# joystick_shield.net
KiCad netlist of a schematic drawn in EAGLE
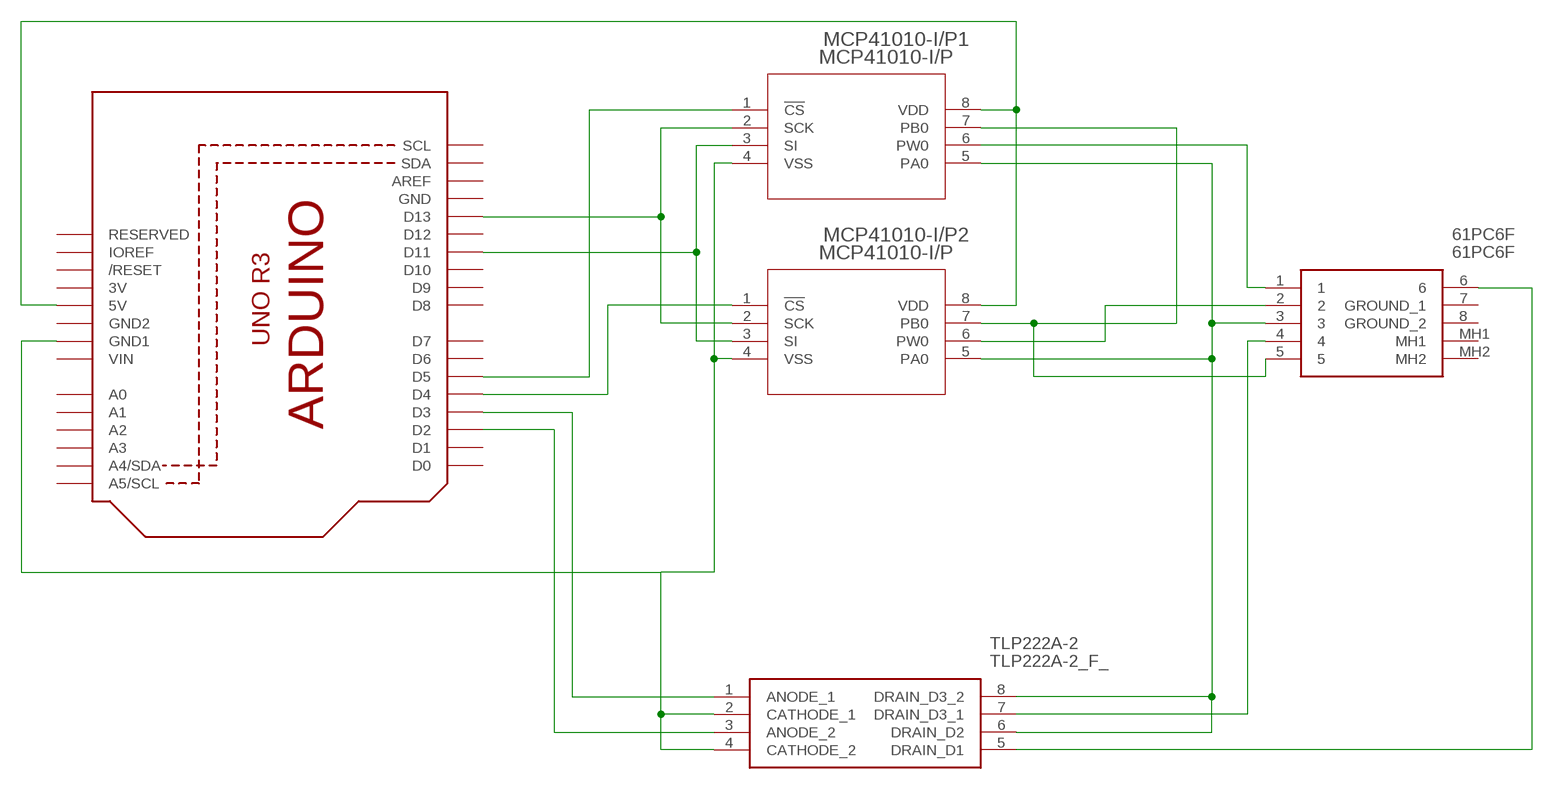
[diagram p0: schematic, sheet 1]

(export (version "E")
  (design (tool "Eeschema 10.0.6"))
  (components
    (comp (ref "61PC6F")
      (value "61PC6F")
      (footprint "eagle-import:61PC6F")
      (fields (field (name "MOUSER_PART_NUMBER") "502-61PC6F"))
      (libsource (lib "eagle-import") (part "61PC6F"))
    )
    (comp (ref "MCP41010-I/P1")
      (value "MCP41010-I/P")
      (footprint "eagle-import:PDIP8_300MC")
      (fields (field (name "COPYRIGHT") "Copyright (C) 2018 Accelerated Designs. All rights reserved"))
      (libsource (lib "eagle-import") (part "MCP41010-I/P"))
    )
    (comp (ref "MCP41010-I/P2")
      (value "MCP41010-I/P")
      (footprint "eagle-import:PDIP8_300MC")
      (fields (field (name "COPYRIGHT") "Copyright (C) 2018 Accelerated Designs. All rights reserved"))
      (libsource (lib "eagle-import") (part "MCP41010-I/P"))
    )
    (comp (ref "TLP222A-2")
      (value "TLP222A-2_F_")
      (footprint "eagle-import:DIP762W60P254L966H485Q8N")
      (fields
        (field (name "MANUFACTURER_PART_NUMBER") "TLP222A-2(F)")
        (field (name "MOUSER_PART_NUMBER") "757-TLP222A-2(F)")
      )
      (libsource (lib "eagle-import") (part "TLP222A-2_F_"))
    )
    (comp (ref "U3")
      (value "ARDUINOR3-BPLACE")
      (footprint "eagle-import:ARDUINOR3-BPLACE")
      (libsource (lib "eagle-import") (part "ARDUINOR3-BPLACE"))
    )
  )
  (nets
    (net (code "1") (name "/3V") (class "Default")
      (node (ref "U3") (pin "3V") (pinfunction "3V_3V") (pintype "power_in"))
    )
    (net (code "2") (name "/GND") (class "Default")
      (node (ref "U3") (pin "GND") (pinfunction "GND_GND") (pintype "power_in"))
    )
    (net (code "3") (name "/GND2") (class "Default")
      (node (ref "U3") (pin "GND2") (pinfunction "GND2_GND2") (pintype "power_in"))
    )
    (net (code "4") (name "/VIN") (class "Default")
      (node (ref "U3") (pin "VIN") (pinfunction "VIN_VIN") (pintype "power_in"))
    )
    (net (code "5") (name "Net-(MCP41010-I/P1-PA0)") (class "Default")
      (node (ref "61PC6F") (pin "3") (pinfunction "3_3") (pintype "bidirectional"))
      (node (ref "MCP41010-I/P1") (pin "5") (pinfunction "PA0_5") (pintype "passive"))
      (node (ref "MCP41010-I/P2") (pin "5") (pinfunction "PA0_5") (pintype "passive"))
      (node (ref "TLP222A-2") (pin "6") (pinfunction "DRAIN_D2_6") (pintype "bidirectional"))
      (node (ref "TLP222A-2") (pin "8") (pinfunction "DRAIN_D3_2_8") (pintype "bidirectional"))
    )
    (net (code "6") (name "Net-(MCP41010-I/P1-PB0)") (class "Default")
      (node (ref "61PC6F") (pin "5") (pinfunction "5_5") (pintype "bidirectional"))
      (node (ref "MCP41010-I/P1") (pin "7") (pinfunction "PB0_7") (pintype "passive"))
      (node (ref "MCP41010-I/P2") (pin "7") (pinfunction "PB0_7") (pintype "passive"))
    )
    (net (code "7") (name "Net-(MCP41010-I/P1-PW0)") (class "Default")
      (node (ref "61PC6F") (pin "1") (pinfunction "1_1") (pintype "bidirectional"))
      (node (ref "MCP41010-I/P1") (pin "6") (pinfunction "PW0_6") (pintype "passive"))
    )
    (net (code "8") (name "Net-(MCP41010-I/P1-SCK)") (class "Default")
      (node (ref "MCP41010-I/P1") (pin "2") (pinfunction "SCK_2") (pintype "passive"))
      (node (ref "MCP41010-I/P2") (pin "2") (pinfunction "SCK_2") (pintype "passive"))
      (node (ref "U3") (pin "D13") (pinfunction "D13_D13") (pintype "bidirectional"))
    )
    (net (code "9") (name "Net-(MCP41010-I/P1-SI)") (class "Default")
      (node (ref "MCP41010-I/P1") (pin "3") (pinfunction "SI_3") (pintype "passive"))
      (node (ref "MCP41010-I/P2") (pin "3") (pinfunction "SI_3") (pintype "passive"))
      (node (ref "U3") (pin "D11") (pinfunction "D11_D11") (pintype "bidirectional"))
    )
    (net (code "10") (name "Net-(MCP41010-I/P1-VDD)") (class "Default")
      (node (ref "MCP41010-I/P1") (pin "8") (pinfunction "VDD_8") (pintype "passive"))
      (node (ref "MCP41010-I/P2") (pin "8") (pinfunction "VDD_8") (pintype "passive"))
      (node (ref "U3") (pin "5V") (pinfunction "5V_5V") (pintype "power_in"))
    )
    (net (code "11") (name "Net-(MCP41010-I/P1-VSS)") (class "Default")
      (node (ref "MCP41010-I/P1") (pin "4") (pinfunction "VSS_4") (pintype "passive"))
      (node (ref "MCP41010-I/P2") (pin "4") (pinfunction "VSS_4") (pintype "passive"))
      (node (ref "TLP222A-2") (pin "2") (pinfunction "CATHODE_1_2") (pintype "bidirectional"))
      (node (ref "TLP222A-2") (pin "4") (pinfunction "CATHODE_2_4") (pintype "bidirectional"))
      (node (ref "U3") (pin "GND1") (pinfunction "GND1_GND1") (pintype "power_in"))
    )
    (net (code "12") (name "Net-(MCP41010-I/P1-~{CS})") (class "Default")
      (node (ref "MCP41010-I/P1") (pin "1") (pinfunction "~{CS}_1") (pintype "passive"))
      (node (ref "U3") (pin "D5") (pinfunction "D5_D5") (pintype "bidirectional"))
    )
    (net (code "13") (name "Net-(MCP41010-I/P2-PW0)") (class "Default")
      (node (ref "61PC6F") (pin "2") (pinfunction "2_2") (pintype "bidirectional"))
      (node (ref "MCP41010-I/P2") (pin "6") (pinfunction "PW0_6") (pintype "passive"))
    )
    (net (code "14") (name "Net-(MCP41010-I/P2-~{CS})") (class "Default")
      (node (ref "MCP41010-I/P2") (pin "1") (pinfunction "~{CS}_1") (pintype "passive"))
      (node (ref "U3") (pin "D4") (pinfunction "D4_D4") (pintype "bidirectional"))
    )
    (net (code "15") (name "Net-(TLP222A-2-ANODE_1)") (class "Default")
      (node (ref "TLP222A-2") (pin "1") (pinfunction "ANODE_1_1") (pintype "bidirectional"))
      (node (ref "U3") (pin "D3") (pinfunction "D3_D3") (pintype "bidirectional"))
    )
    (net (code "16") (name "Net-(TLP222A-2-ANODE_2)") (class "Default")
      (node (ref "TLP222A-2") (pin "3") (pinfunction "ANODE_2_3") (pintype "bidirectional"))
      (node (ref "U3") (pin "D2") (pinfunction "D2_D2") (pintype "bidirectional"))
    )
    (net (code "17") (name "Net-(TLP222A-2-DRAIN_D1)") (class "Default")
      (node (ref "61PC6F") (pin "6") (pinfunction "6_6") (pintype "bidirectional"))
      (node (ref "TLP222A-2") (pin "5") (pinfunction "DRAIN_D1_5") (pintype "bidirectional"))
    )
    (net (code "18") (name "Net-(TLP222A-2-DRAIN_D3_1)") (class "Default")
      (node (ref "61PC6F") (pin "4") (pinfunction "4_4") (pintype "bidirectional"))
      (node (ref "TLP222A-2") (pin "7") (pinfunction "DRAIN_D3_1_7") (pintype "bidirectional"))
    )
    (net (code "19") (name "unconnected-(61PC6F-GROUND_1-Pad7)") (class "Default")
      (node (ref "61PC6F") (pin "7") (pinfunction "GROUND_1_7") (pintype "bidirectional"))
    )
    (net (code "20") (name "unconnected-(61PC6F-GROUND_2-Pad8)") (class "Default")
      (node (ref "61PC6F") (pin "8") (pinfunction "GROUND_2_8") (pintype "bidirectional"))
    )
    (net (code "21") (name "unconnected-(61PC6F-PadMH1)") (class "Default")
      (node (ref "61PC6F") (pin "MH1") (pinfunction "MH1_MH1") (pintype "bidirectional"))
    )
    (net (code "22") (name "unconnected-(61PC6F-PadMH2)") (class "Default")
      (node (ref "61PC6F") (pin "MH2") (pinfunction "MH2_MH2") (pintype "bidirectional"))
    )
    (net (code "23") (name "unconnected-(U3-A4{slash}SDA-PadA4)") (class "Default")
      (node (ref "U3") (pin "A4") (pinfunction "A4/SDA_A4") (pintype "bidirectional"))
    )
    (net (code "24") (name "unconnected-(U3-A5{slash}SCL-PadA5)") (class "Default")
      (node (ref "U3") (pin "A5") (pinfunction "A5/SCL_A5") (pintype "bidirectional"))
    )
    (net (code "25") (name "unconnected-(U3-PadA0)") (class "Default")
      (node (ref "U3") (pin "A0") (pinfunction "A0_A0") (pintype "bidirectional"))
    )
    (net (code "26") (name "unconnected-(U3-PadA1)") (class "Default")
      (node (ref "U3") (pin "A1") (pinfunction "A1_A1") (pintype "bidirectional"))
    )
    (net (code "27") (name "unconnected-(U3-PadA2)") (class "Default")
      (node (ref "U3") (pin "A2") (pinfunction "A2_A2") (pintype "bidirectional"))
    )
    (net (code "28") (name "unconnected-(U3-PadA3)") (class "Default")
      (node (ref "U3") (pin "A3") (pinfunction "A3_A3") (pintype "bidirectional"))
    )
    (net (code "29") (name "unconnected-(U3-PadAREF)") (class "Default")
      (node (ref "U3") (pin "AREF") (pinfunction "AREF_AREF") (pintype "bidirectional"))
    )
    (net (code "30") (name "unconnected-(U3-PadD0)") (class "Default")
      (node (ref "U3") (pin "D0") (pinfunction "D0_D0") (pintype "bidirectional"))
    )
    (net (code "31") (name "unconnected-(U3-PadD1)") (class "Default")
      (node (ref "U3") (pin "D1") (pinfunction "D1_D1") (pintype "bidirectional"))
    )
    (net (code "32") (name "unconnected-(U3-PadD6)") (class "Default")
      (node (ref "U3") (pin "D6") (pinfunction "D6_D6") (pintype "bidirectional"))
    )
    (net (code "33") (name "unconnected-(U3-PadD7)") (class "Default")
      (node (ref "U3") (pin "D7") (pinfunction "D7_D7") (pintype "bidirectional"))
    )
    (net (code "34") (name "unconnected-(U3-PadD8)") (class "Default")
      (node (ref "U3") (pin "D8") (pinfunction "D8_D8") (pintype "bidirectional"))
    )
    (net (code "35") (name "unconnected-(U3-PadD9)") (class "Default")
      (node (ref "U3") (pin "D9") (pinfunction "D9_D9") (pintype "bidirectional"))
    )
    (net (code "36") (name "unconnected-(U3-PadD10)") (class "Default")
      (node (ref "U3") (pin "D10") (pinfunction "D10_D10") (pintype "bidirectional"))
    )
    (net (code "37") (name "unconnected-(U3-PadD12)") (class "Default")
      (node (ref "U3") (pin "D12") (pinfunction "D12_D12") (pintype "bidirectional"))
    )
    (net (code "38") (name "unconnected-(U3-PadIOREF)") (class "Default")
      (node (ref "U3") (pin "IOREF") (pinfunction "IOREF_IOREF") (pintype "output"))
    )
    (net (code "39") (name "unconnected-(U3-PadRESERVED)") (class "Default")
      (node (ref "U3") (pin "RESERVED") (pinfunction "RESERVED_RESERVED") (pintype "no_connect"))
    )
    (net (code "40") (name "unconnected-(U3-PadSCL)") (class "Default")
      (node (ref "U3") (pin "SCL") (pinfunction "SCL_SCL") (pintype "bidirectional"))
    )
    (net (code "41") (name "unconnected-(U3-PadSDA)") (class "Default")
      (node (ref "U3") (pin "SDA") (pinfunction "SDA_SDA") (pintype "bidirectional"))
    )
    (net (code "42") (name "unconnected-(U3-{slash}RESET-PadRESET)") (class "Default")
      (node (ref "U3") (pin "RESET") (pinfunction "/RESET_RESET") (pintype "bidirectional"))
    )
  )
)
